# PCBV4.net
KiCad netlist of a schematic drawn in EAGLE
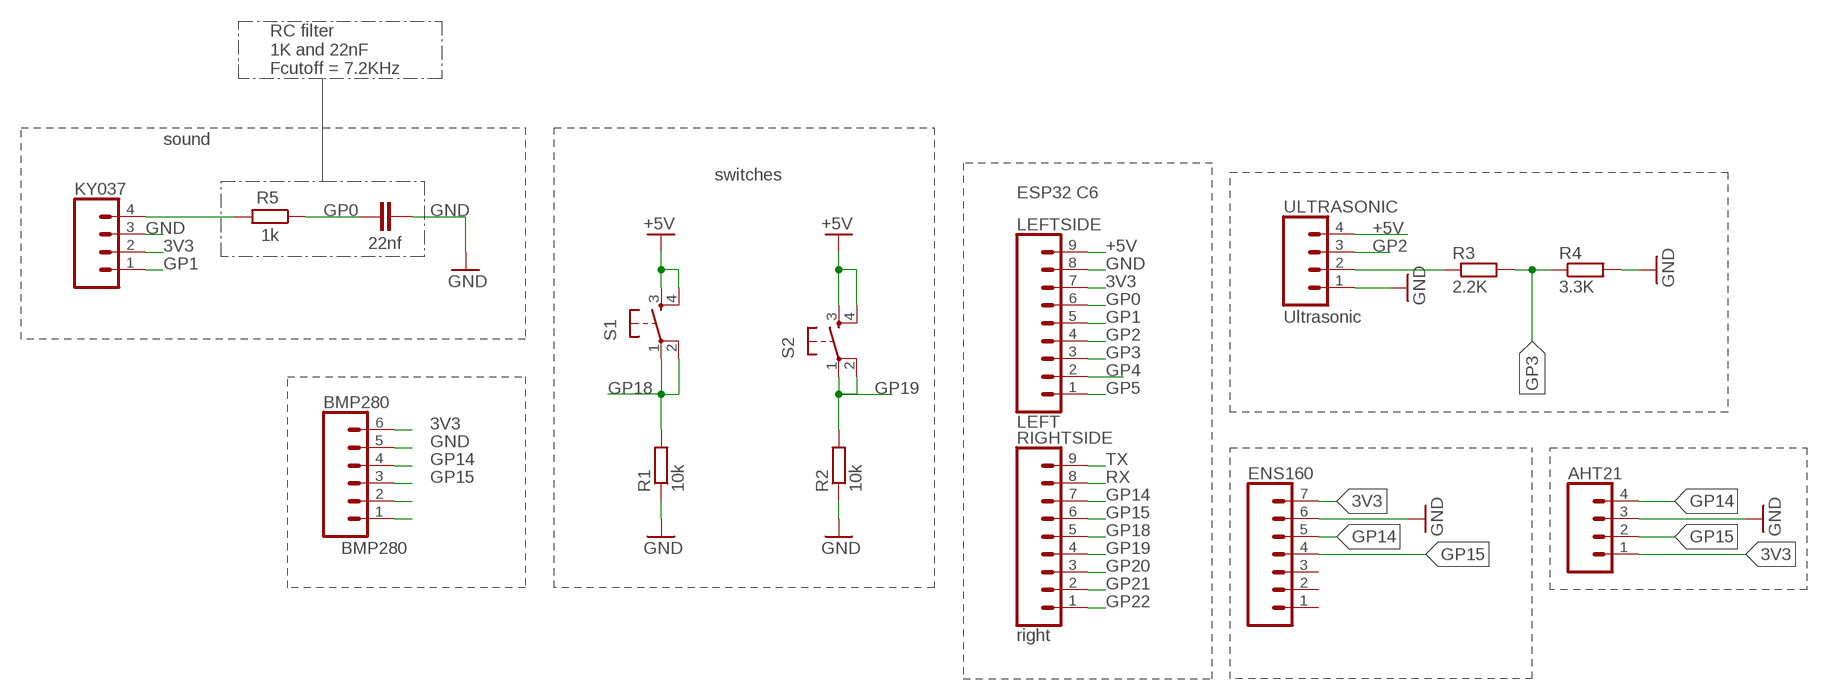
[diagram p0: schematic, sheet 1]

(export (version "E")
  (design (tool "Eeschema 10.0.6"))
  (components
    (comp (ref "AHT21")
      (value "CONN_04LONGPADS")
      (footprint "eagle-import:1X04_LONGPADS")
      (libsource (lib "eagle-import") (part "CONN_04LONGPADS"))
    )
    (comp (ref "BMP280")
      (value "BMP280")
      (footprint "eagle-import:SPARKFUN-CONNECTORS_1X06_LONGPADS")
      (libsource (lib "eagle-import") (part "SPARKFUN-CONNECTORS_CONN_06LONGPADS"))
    )
    (comp (ref "C1")
      (value "22nf")
      (footprint "eagle-import:CAPACITOR-WIMA_C2.5-2")
      (libsource (lib "eagle-import") (part "CAPACITOR-WIMA_C2.5/2"))
    )
    (comp (ref "ENS160")
      (value "CONN_07")
      (footprint "eagle-import:1X07")
      (libsource (lib "eagle-import") (part "CONN_07"))
    )
    (comp (ref "KY037")
      (value "1X04_SMD_STRAIGHT_COMBO")
      (footprint "eagle-import:1X04_LONGPADS")
      (libsource (lib "eagle-import") (part "CONN_04LONGPADS"))
    )
    (comp (ref "LEFTSIDE")
      (value "LEFT")
      (footprint "eagle-import:1X09")
      (libsource (lib "eagle-import") (part "CONN_09"))
    )
    (comp (ref "R1")
      (value "10k")
      (footprint "eagle-import:0207_10")
      (libsource (lib "eagle-import") (part "R-EU_0207/10"))
    )
    (comp (ref "R2")
      (value "10k")
      (footprint "eagle-import:0207_10")
      (libsource (lib "eagle-import") (part "R-EU_0207/10"))
    )
    (comp (ref "R3")
      (value "2.2K")
      (footprint "eagle-import:0207_10")
      (libsource (lib "eagle-import") (part "R-EU_0207/10"))
    )
    (comp (ref "R4")
      (value "3.3K")
      (footprint "eagle-import:0207_10")
      (libsource (lib "eagle-import") (part "R-EU_0207/10"))
    )
    (comp (ref "R5")
      (value "1k")
      (footprint "eagle-import:0207_10")
      (libsource (lib "eagle-import") (part "R-EU_0207/10"))
    )
    (comp (ref "RIGHTSIDE")
      (value "right")
      (footprint "eagle-import:1X09")
      (libsource (lib "eagle-import") (part "CONN_09"))
    )
    (comp (ref "S1")
      (value "EL311-ROBOT_SPARKFUN-ELECTROMECHANICAL_TAC_SWITCHPTH")
      (footprint "eagle-import:EL311-ROBOT_SPARKFUN-ELECTROMECHANICAL_TACTILE-PTH")
      (libsource (lib "eagle-import") (part "EL311-ROBOT_SPARKFUN-ELECTROMECHANICAL_TAC_SWITCHPTH"))
    )
    (comp (ref "S2")
      (value "EL311-ROBOT_SPARKFUN-ELECTROMECHANICAL_TAC_SWITCHPTH")
      (footprint "eagle-import:EL311-ROBOT_SPARKFUN-ELECTROMECHANICAL_TACTILE-PTH")
      (libsource (lib "eagle-import") (part "EL311-ROBOT_SPARKFUN-ELECTROMECHANICAL_TAC_SWITCHPTH"))
    )
    (comp (ref "ULTRASONIC")
      (value "1X04_SMD_STRAIGHT_COMBO")
      (footprint "eagle-import:1X04_LONGPADS")
      (libsource (lib "eagle-import") (part "CONN_04LONGPADS"))
    )
  )
  (nets
    (net (code "1") (name "+5V") (class "Default")
      (node (ref "LEFTSIDE") (pin "9") (pinfunction "9_9") (pintype "passive"))
      (node (ref "S1") (pin "3") (pinfunction "3_3") (pintype "passive"))
      (node (ref "S1") (pin "4") (pinfunction "4_4") (pintype "passive"))
      (node (ref "S2") (pin "3") (pinfunction "3_3") (pintype "passive"))
      (node (ref "S2") (pin "4") (pinfunction "4_4") (pintype "passive"))
      (node (ref "ULTRASONIC") (pin "4") (pinfunction "4_4") (pintype "passive"))
    )
    (net (code "2") (name "/GP0") (class "Default")
      (node (ref "C1") (pin "1") (pinfunction "1_1") (pintype "passive"))
      (node (ref "LEFTSIDE") (pin "6") (pinfunction "6_6") (pintype "passive"))
      (node (ref "R5") (pin "1") (pinfunction "1_1") (pintype "passive"))
    )
    (net (code "3") (name "/GP1") (class "Default")
      (node (ref "KY037") (pin "1") (pinfunction "1_1") (pintype "passive"))
      (node (ref "LEFTSIDE") (pin "5") (pinfunction "5_5") (pintype "passive"))
    )
    (net (code "4") (name "/GP2") (class "Default")
      (node (ref "LEFTSIDE") (pin "4") (pinfunction "4_4") (pintype "passive"))
      (node (ref "ULTRASONIC") (pin "3") (pinfunction "3_3") (pintype "passive"))
    )
    (net (code "5") (name "/GP4") (class "Default")
      (node (ref "LEFTSIDE") (pin "2") (pinfunction "2_2") (pintype "passive"))
    )
    (net (code "6") (name "/GP5") (class "Default")
      (node (ref "LEFTSIDE") (pin "1") (pinfunction "1_1") (pintype "passive"))
    )
    (net (code "7") (name "/GP18") (class "Default")
      (node (ref "R1") (pin "2") (pinfunction "2_2") (pintype "passive"))
      (node (ref "RIGHTSIDE") (pin "5") (pinfunction "5_5") (pintype "passive"))
      (node (ref "S1") (pin "1") (pinfunction "1_1") (pintype "passive"))
      (node (ref "S1") (pin "2") (pinfunction "2_2") (pintype "passive"))
    )
    (net (code "8") (name "/GP19") (class "Default")
      (node (ref "R2") (pin "2") (pinfunction "2_2") (pintype "passive"))
      (node (ref "RIGHTSIDE") (pin "4") (pinfunction "4_4") (pintype "passive"))
      (node (ref "S2") (pin "1") (pinfunction "1_1") (pintype "passive"))
      (node (ref "S2") (pin "2") (pinfunction "2_2") (pintype "passive"))
    )
    (net (code "9") (name "/GP20") (class "Default")
      (node (ref "RIGHTSIDE") (pin "3") (pinfunction "3_3") (pintype "passive"))
    )
    (net (code "10") (name "/GP21") (class "Default")
      (node (ref "RIGHTSIDE") (pin "2") (pinfunction "2_2") (pintype "passive"))
    )
    (net (code "11") (name "/GP22") (class "Default")
      (node (ref "RIGHTSIDE") (pin "1") (pinfunction "1_1") (pintype "passive"))
    )
    (net (code "12") (name "/RX") (class "Default")
      (node (ref "RIGHTSIDE") (pin "8") (pinfunction "8_8") (pintype "passive"))
    )
    (net (code "13") (name "/TX") (class "Default")
      (node (ref "RIGHTSIDE") (pin "9") (pinfunction "9_9") (pintype "passive"))
    )
    (net (code "14") (name "3V3") (class "Default")
      (node (ref "AHT21") (pin "1") (pinfunction "1_1") (pintype "passive"))
      (node (ref "BMP280") (pin "6") (pinfunction "6_6") (pintype "passive"))
      (node (ref "ENS160") (pin "7") (pinfunction "7_7") (pintype "passive"))
      (node (ref "KY037") (pin "2") (pinfunction "2_2") (pintype "passive"))
      (node (ref "LEFTSIDE") (pin "7") (pinfunction "7_7") (pintype "passive"))
    )
    (net (code "15") (name "GND") (class "Default")
      (node (ref "AHT21") (pin "3") (pinfunction "3_3") (pintype "passive"))
      (node (ref "BMP280") (pin "5") (pinfunction "5_5") (pintype "passive"))
      (node (ref "C1") (pin "2") (pinfunction "2_2") (pintype "passive"))
      (node (ref "ENS160") (pin "6") (pinfunction "6_6") (pintype "passive"))
      (node (ref "KY037") (pin "3") (pinfunction "3_3") (pintype "passive"))
      (node (ref "LEFTSIDE") (pin "8") (pinfunction "8_8") (pintype "passive"))
      (node (ref "R1") (pin "1") (pinfunction "1_1") (pintype "passive"))
      (node (ref "R2") (pin "1") (pinfunction "1_1") (pintype "passive"))
      (node (ref "R4") (pin "2") (pinfunction "2_2") (pintype "passive"))
      (node (ref "ULTRASONIC") (pin "1") (pinfunction "1_1") (pintype "passive"))
    )
    (net (code "16") (name "GP3") (class "Default")
      (node (ref "LEFTSIDE") (pin "3") (pinfunction "3_3") (pintype "passive"))
      (node (ref "R3") (pin "2") (pinfunction "2_2") (pintype "passive"))
      (node (ref "R4") (pin "1") (pinfunction "1_1") (pintype "passive"))
    )
    (net (code "17") (name "GP14") (class "Default")
      (node (ref "AHT21") (pin "4") (pinfunction "4_4") (pintype "passive"))
      (node (ref "BMP280") (pin "4") (pinfunction "4_4") (pintype "passive"))
      (node (ref "ENS160") (pin "5") (pinfunction "5_5") (pintype "passive"))
      (node (ref "RIGHTSIDE") (pin "7") (pinfunction "7_7") (pintype "passive"))
    )
    (net (code "18") (name "GP15") (class "Default")
      (node (ref "AHT21") (pin "2") (pinfunction "2_2") (pintype "passive"))
      (node (ref "BMP280") (pin "3") (pinfunction "3_3") (pintype "passive"))
      (node (ref "ENS160") (pin "4") (pinfunction "4_4") (pintype "passive"))
      (node (ref "RIGHTSIDE") (pin "6") (pinfunction "6_6") (pintype "passive"))
    )
    (net (code "19") (name "Net-(KY037-Pad4)") (class "Default")
      (node (ref "KY037") (pin "4") (pinfunction "4_4") (pintype "passive"))
      (node (ref "R5") (pin "2") (pinfunction "2_2") (pintype "passive"))
    )
    (net (code "20") (name "Net-(R3-Pad1)") (class "Default")
      (node (ref "R3") (pin "1") (pinfunction "1_1") (pintype "passive"))
      (node (ref "ULTRASONIC") (pin "2") (pinfunction "2_2") (pintype "passive"))
    )
    (net (code "21") (name "unconnected-(BMP280-Pad1)") (class "Default")
      (node (ref "BMP280") (pin "1") (pinfunction "1_1") (pintype "passive"))
    )
    (net (code "22") (name "unconnected-(BMP280-Pad2)") (class "Default")
      (node (ref "BMP280") (pin "2") (pinfunction "2_2") (pintype "passive"))
    )
    (net (code "23") (name "unconnected-(ENS160-Pad1)") (class "Default")
      (node (ref "ENS160") (pin "1") (pinfunction "1_1") (pintype "passive"))
    )
    (net (code "24") (name "unconnected-(ENS160-Pad2)") (class "Default")
      (node (ref "ENS160") (pin "2") (pinfunction "2_2") (pintype "passive"))
    )
    (net (code "25") (name "unconnected-(ENS160-Pad3)") (class "Default")
      (node (ref "ENS160") (pin "3") (pinfunction "3_3") (pintype "passive"))
    )
  )
)
